# SparkFun_Analog_MEMS_Microphone_Breakout.net
KiCad netlist of a schematic drawn in EAGLE
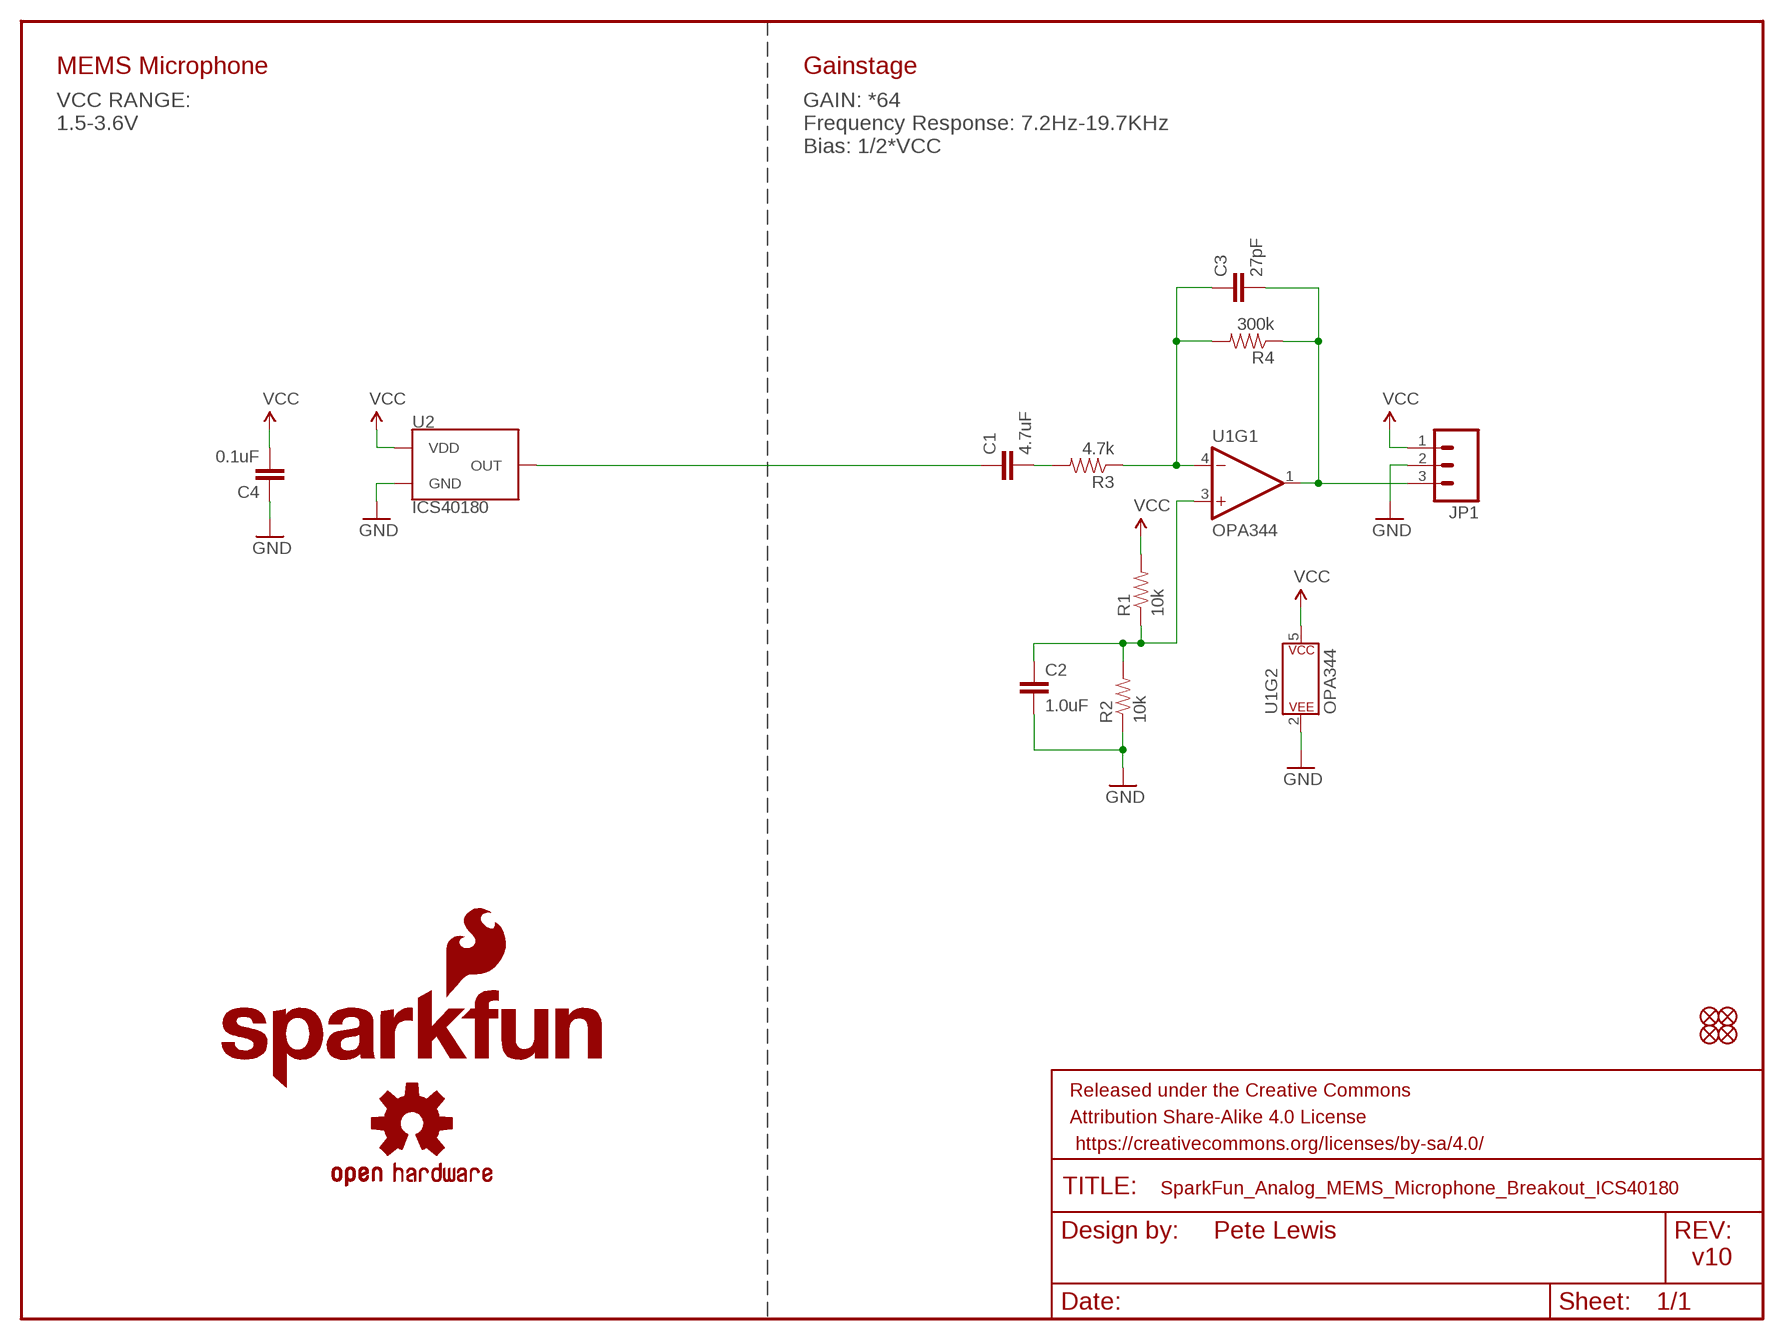
[diagram p0: schematic, sheet 1]

(export (version "E")
  (design (tool "Eeschema 10.0.6"))
  (components
    (comp (ref "C1")
      (value "4.7uF")
      (footprint "eagle-import:0603")
      (libsource (lib "eagle-import") (part "4.7UF-0603-6.3V-(10%)"))
    )
    (comp (ref "C2")
      (value "1.0uF")
      (footprint "eagle-import:0603")
      (libsource (lib "eagle-import") (part "1.0UF-0603-16V-10%"))
    )
    (comp (ref "C3")
      (value "27pF")
      (footprint "eagle-import:0603")
      (libsource (lib "eagle-import") (part "27PF-0603-50V-5%"))
    )
    (comp (ref "C4")
      (value "0.1uF")
      (footprint "eagle-import:0603")
      (libsource (lib "eagle-import") (part "0.1UF-0603-25V-(+80/-20%)"))
    )
    (comp (ref "FD1")
      (value "FIDUCIALUFIDUCIAL")
      (footprint "eagle-import:FIDUCIAL-MICRO")
      (libsource (lib "eagle-import") (part "FIDUCIALUFIDUCIAL"))
    )
    (comp (ref "FD2")
      (value "FIDUCIALUFIDUCIAL")
      (footprint "eagle-import:FIDUCIAL-MICRO")
      (libsource (lib "eagle-import") (part "FIDUCIALUFIDUCIAL"))
    )
    (comp (ref "FD3")
      (value "FIDUCIALUFIDUCIAL")
      (footprint "eagle-import:FIDUCIAL-MICRO")
      (libsource (lib "eagle-import") (part "FIDUCIALUFIDUCIAL"))
    )
    (comp (ref "FD4")
      (value "FIDUCIALUFIDUCIAL")
      (footprint "eagle-import:FIDUCIAL-MICRO")
      (libsource (lib "eagle-import") (part "FIDUCIALUFIDUCIAL"))
    )
    (comp (ref "FRAME2")
      (value "FRAME-LETTER")
      (footprint "eagle-import:CREATIVE_COMMONS")
      (libsource (lib "eagle-import") (part "FRAME-LETTER"))
    )
    (comp (ref "JP1")
      (value "CONN_031X03_NO_SILK")
      (footprint "eagle-import:1X03_NO_SILK")
      (libsource (lib "eagle-import") (part "CONN_031X03_NO_SILK"))
    )
    (comp (ref "LOGO1")
      (value "SFE_LOGO_FLAME.1_INCH")
      (footprint "eagle-import:SFE_LOGO_FLAME_.1")
      (libsource (lib "eagle-import") (part "SFE_LOGO_FLAME.1_INCH"))
    )
    (comp (ref "LOGO2")
      (value "OSHW-LOGOMINI")
      (footprint "eagle-import:OSHW-LOGO-MINI")
      (libsource (lib "eagle-import") (part "OSHW-LOGOMINI"))
    )
    (comp (ref "R1")
      (value "10k")
      (footprint "eagle-import:0603")
      (libsource (lib "eagle-import") (part "10KOHM-0603-1/10W-1%"))
    )
    (comp (ref "R2")
      (value "10k")
      (footprint "eagle-import:0603")
      (libsource (lib "eagle-import") (part "10KOHM-0603-1/10W-1%"))
    )
    (comp (ref "R3")
      (value "4.7k")
      (footprint "eagle-import:0603")
      (libsource (lib "eagle-import") (part "4.7KOHM-0603-1/10W-1%"))
    )
    (comp (ref "R4")
      (value "300k")
      (footprint "eagle-import:0603")
      (libsource (lib "eagle-import") (part "300KOHM-0603-1/10W-1%"))
    )
    (comp (ref "U1")
      (value "OPA344")
      (footprint "eagle-import:SOT23-5")
      (libsource (lib "eagle-import") (part "OPA344"))
    )
    (comp (ref "U2")
      (value "ICS40180")
      (footprint "eagle-import:ICS40180")
      (libsource (lib "eagle-import") (part "ICS40180"))
    )
  )
  (nets
    (net (code "1") (name "GND") (class "Default")
      (node (ref "C2") (pin "2") (pinfunction "2_2") (pintype "passive"))
      (node (ref "C4") (pin "1") (pinfunction "1_1") (pintype "passive"))
      (node (ref "JP1") (pin "2") (pinfunction "2_2") (pintype "passive"))
      (node (ref "R2") (pin "1") (pinfunction "1_1") (pintype "passive"))
      (node (ref "U1") (pin "2") (pinfunction "P$V-_2") (pintype "bidirectional"))
      (node (ref "U2") (pin "2") (pinfunction "GND_2") (pintype "bidirectional"))
      (node (ref "U2") (pin "3") (pinfunction "GND_3") (pintype "bidirectional"))
      (node (ref "U2") (pin "4") (pinfunction "GND_4") (pintype "bidirectional"))
    )
    (net (code "2") (name "Net-(C1-Pad2)") (class "Default")
      (node (ref "C1") (pin "2") (pinfunction "2_2") (pintype "passive"))
      (node (ref "R3") (pin "2") (pinfunction "2_2") (pintype "passive"))
    )
    (net (code "3") (name "Net-(U1A-+IN)") (class "Default")
      (node (ref "C2") (pin "1") (pinfunction "1_1") (pintype "passive"))
      (node (ref "R1") (pin "1") (pinfunction "1_1") (pintype "passive"))
      (node (ref "R2") (pin "2") (pinfunction "2_2") (pintype "passive"))
      (node (ref "U1") (pin "3") (pinfunction "+IN_3") (pintype "input"))
    )
    (net (code "4") (name "Net-(U1A--IN)") (class "Default")
      (node (ref "C3") (pin "1") (pinfunction "1_1") (pintype "passive"))
      (node (ref "R3") (pin "1") (pinfunction "1_1") (pintype "passive"))
      (node (ref "R4") (pin "2") (pinfunction "2_2") (pintype "passive"))
      (node (ref "U1") (pin "4") (pinfunction "-IN_4") (pintype "input"))
    )
    (net (code "5") (name "Net-(U1A-OUT)") (class "Default")
      (node (ref "C3") (pin "2") (pinfunction "2_2") (pintype "passive"))
      (node (ref "JP1") (pin "3") (pinfunction "3_3") (pintype "passive"))
      (node (ref "R4") (pin "1") (pinfunction "1_1") (pintype "passive"))
      (node (ref "U1") (pin "1") (pinfunction "OUT_1") (pintype "output"))
    )
    (net (code "6") (name "Net-(U2-OUT)") (class "Default")
      (node (ref "C1") (pin "1") (pinfunction "1_1") (pintype "passive"))
      (node (ref "U2") (pin "1") (pinfunction "OUT_1") (pintype "bidirectional"))
    )
    (net (code "7") (name "VCC") (class "Default")
      (node (ref "C4") (pin "2") (pinfunction "2_2") (pintype "passive"))
      (node (ref "JP1") (pin "1") (pinfunction "1_1") (pintype "passive"))
      (node (ref "R1") (pin "2") (pinfunction "2_2") (pintype "passive"))
      (node (ref "U1") (pin "5") (pinfunction "P$V+_5") (pintype "bidirectional"))
      (node (ref "U2") (pin "5") (pinfunction "VDD_5") (pintype "bidirectional"))
    )
  )
)
